# connector_schematic.net
KiCad netlist of a schematic drawn in EAGLE
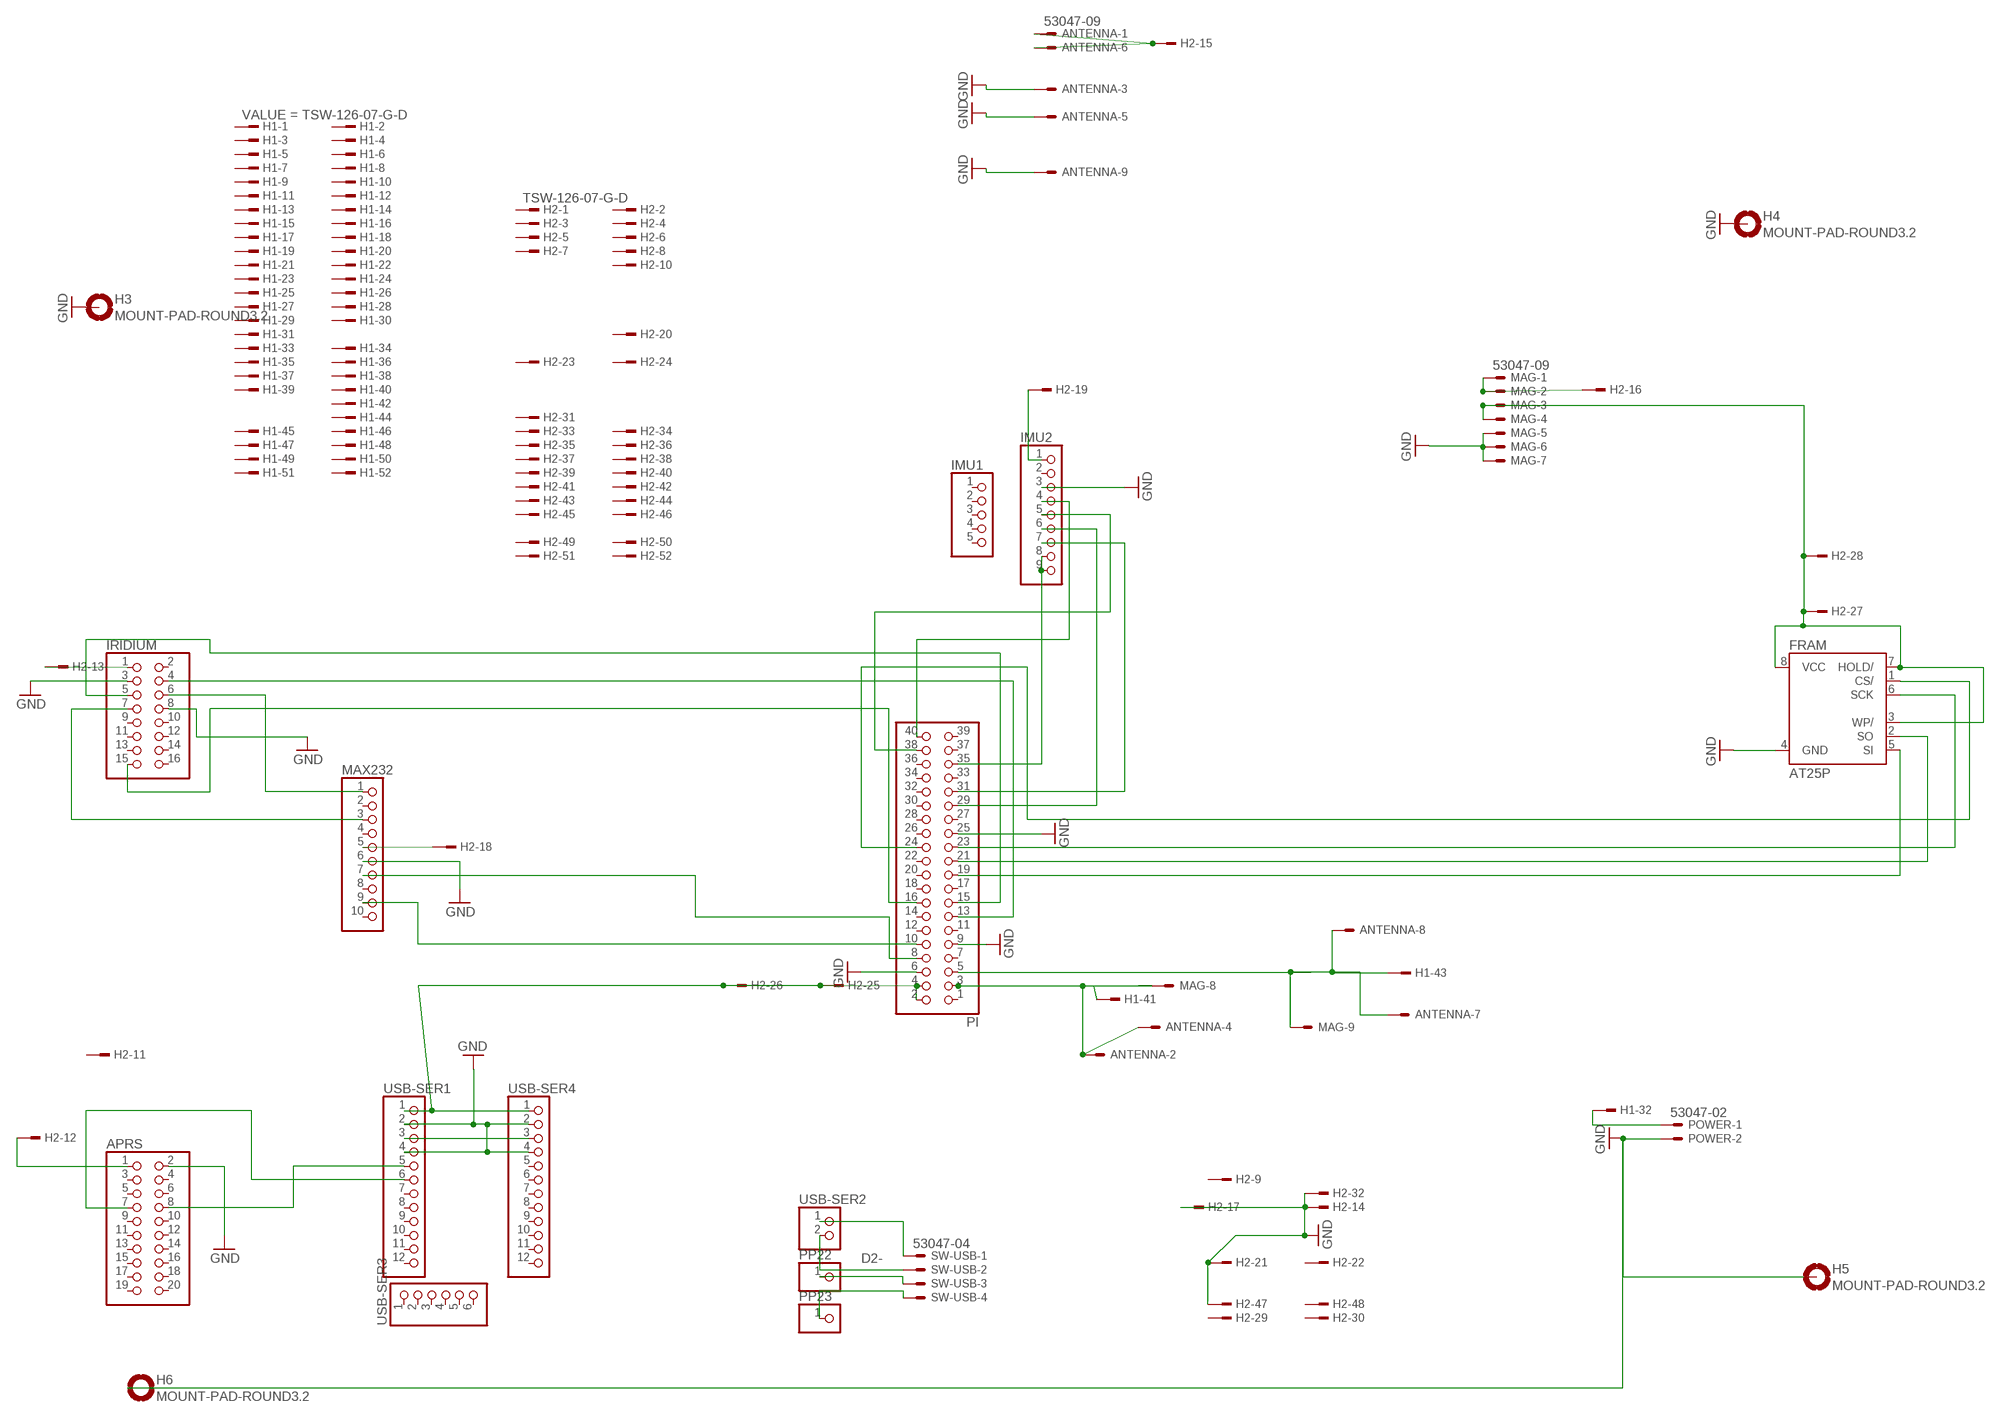
[diagram p0: schematic, sheet 1]

(export (version "E")
  (design (tool "Eeschema 10.0.6"))
  (components
    (comp (ref "ANTENNA")
      (value "53047-09")
      (footprint "eagle-import:53047-09")
      (fields (field (name "MF") "MOLEX") (field (name "MPN") "53047-0910"))
      (libsource (lib "eagle-import") (part "53?-09047"))
    )
    (comp (ref "APRS")
      (value "PINHD-2X10")
      (footprint "eagle-import:2X10")
      (libsource (lib "eagle-import") (part "PINHD-2X10"))
    )
    (comp (ref "FRAM")
      (value "AT25P")
      (footprint "eagle-import:DIL08")
      (fields (field (name "MPN") "CAT25040LI-G"))
      (libsource (lib "eagle-import") (part "AT25P"))
    )
    (comp (ref "H1")
      (value "TSW-126-07-G-D")
      (footprint "eagle-import:TSW-126-XX-G-D")
      (fields (field (name "MF") "Samtec Inc."))
      (libsource (lib "eagle-import") (part "TSW-126--G-D07"))
    )
    (comp (ref "H2")
      (value "TSW-126-07-G-D")
      (footprint "eagle-import:TSW-126-XX-G-D")
      (fields (field (name "MF") "Samtec Inc."))
      (libsource (lib "eagle-import") (part "TSW-126--G-D07"))
    )
    (comp (ref "H3")
      (value "MOUNT-PAD-ROUND3.2")
      (footprint "eagle-import:3,2-PAD")
      (libsource (lib "eagle-import") (part "MOUNT-PAD-ROUND3.2"))
    )
    (comp (ref "H4")
      (value "MOUNT-PAD-ROUND3.2")
      (footprint "eagle-import:3,2-PAD")
      (libsource (lib "eagle-import") (part "MOUNT-PAD-ROUND3.2"))
    )
    (comp (ref "H5")
      (value "MOUNT-PAD-ROUND3.2")
      (footprint "eagle-import:3,2-PAD")
      (libsource (lib "eagle-import") (part "MOUNT-PAD-ROUND3.2"))
    )
    (comp (ref "H6")
      (value "MOUNT-PAD-ROUND3.2")
      (footprint "eagle-import:3,2-PAD")
      (libsource (lib "eagle-import") (part "MOUNT-PAD-ROUND3.2"))
    )
    (comp (ref "IMU1")
      (value "PINHD-1X5")
      (footprint "eagle-import:1X05")
      (libsource (lib "eagle-import") (part "PINHD-1X5"))
    )
    (comp (ref "IMU2")
      (value "PINHD-1X9")
      (footprint "eagle-import:1X09")
      (libsource (lib "eagle-import") (part "PINHD-1X9"))
    )
    (comp (ref "IRIDIUM")
      (value "PINHD-2X8")
      (footprint "eagle-import:2X08")
      (libsource (lib "eagle-import") (part "PINHD-2X8"))
    )
    (comp (ref "MAG")
      (value "53047-09")
      (footprint "eagle-import:53047-09")
      (fields (field (name "MF") "MOLEX") (field (name "MPN") "53047-0910"))
      (libsource (lib "eagle-import") (part "53?-09047"))
    )
    (comp (ref "MAX232")
      (value "PINHD-1X10")
      (footprint "eagle-import:1X10")
      (libsource (lib "eagle-import") (part "PINHD-1X10"))
    )
    (comp (ref "PI")
      (value "PINHD-2X20")
      (footprint "eagle-import:2X20")
      (libsource (lib "eagle-import") (part "PINHD-2X20"))
    )
    (comp (ref "POWER")
      (value "53047-02")
      (footprint "eagle-import:53047-02")
      (fields (field (name "MF") "MOLEX") (field (name "MPN") "53047-0210"))
      (libsource (lib "eagle-import") (part "53?-02047"))
    )
    (comp (ref "PP22")
      (value "PINHD-1X1")
      (footprint "eagle-import:1X01")
      (libsource (lib "eagle-import") (part "PINHD-1X1"))
    )
    (comp (ref "PP23")
      (value "PINHD-1X1")
      (footprint "eagle-import:1X01")
      (libsource (lib "eagle-import") (part "PINHD-1X1"))
    )
    (comp (ref "SW-USB")
      (value "53047-04")
      (footprint "eagle-import:53047-04")
      (fields (field (name "MF") "WALDOM/MOLEX") (field (name "MPN") "53047-0410"))
      (libsource (lib "eagle-import") (part "53?-04047"))
    )
    (comp (ref "USB-SER1")
      (value "PINHD-1X12")
      (footprint "eagle-import:1X12")
      (libsource (lib "eagle-import") (part "PINHD-1X12"))
    )
    (comp (ref "USB-SER2")
      (value "PINHD-1X2")
      (footprint "eagle-import:1X02")
      (libsource (lib "eagle-import") (part "PINHD-1X2"))
    )
    (comp (ref "USB-SER3")
      (value "PINHD-1X6")
      (footprint "eagle-import:1X06")
      (libsource (lib "eagle-import") (part "PINHD-1X6"))
    )
    (comp (ref "USB-SER4")
      (value "PINHD-1X12")
      (footprint "eagle-import:1X12")
      (libsource (lib "eagle-import") (part "PINHD-1X12"))
    )
  )
  (nets
    (net (code "1") (name "/D2-") (class "Default")
      (node (ref "SW-USB") (pin "2") (pinfunction "S_2") (pintype "passive"))
      (node (ref "USB-SER2") (pin "2") (pinfunction "2_2") (pintype "passive"))
    )
    (net (code "2") (name "GND") (class "Default")
      (node (ref "ANTENNA") (pin "3") (pinfunction "S_3") (pintype "passive"))
      (node (ref "ANTENNA") (pin "5") (pinfunction "S_5") (pintype "passive"))
      (node (ref "ANTENNA") (pin "9") (pinfunction "S_9") (pintype "passive"))
      (node (ref "APRS") (pin "2") (pinfunction "2_2") (pintype "passive"))
      (node (ref "FRAM") (pin "4") (pinfunction "GND_4") (pintype "power_in"))
      (node (ref "H2") (pin "14") (pinfunction "1_14") (pintype "passive"))
      (node (ref "H2") (pin "17") (pinfunction "1_17") (pintype "passive"))
      (node (ref "H2") (pin "21") (pinfunction "1_21") (pintype "passive"))
      (node (ref "H2") (pin "32") (pinfunction "1_32") (pintype "passive"))
      (node (ref "H2") (pin "47") (pinfunction "1_47") (pintype "passive"))
      (node (ref "H3") (pin "B3,2") (pinfunction "MOUNT_B3,2") (pintype "passive"))
      (node (ref "H4") (pin "B3,2") (pinfunction "MOUNT_B3,2") (pintype "passive"))
      (node (ref "H5") (pin "B3,2") (pinfunction "MOUNT_B3,2") (pintype "passive"))
      (node (ref "H6") (pin "B3,2") (pinfunction "MOUNT_B3,2") (pintype "passive"))
      (node (ref "IMU2") (pin "3") (pinfunction "3_3") (pintype "passive"))
      (node (ref "IRIDIUM") (pin "3") (pinfunction "3_3") (pintype "passive"))
      (node (ref "IRIDIUM") (pin "8") (pinfunction "8_8") (pintype "passive"))
      (node (ref "MAG") (pin "5") (pinfunction "S_5") (pintype "passive"))
      (node (ref "MAG") (pin "6") (pinfunction "S_6") (pintype "passive"))
      (node (ref "MAG") (pin "7") (pinfunction "S_7") (pintype "passive"))
      (node (ref "MAX232") (pin "6") (pinfunction "6_6") (pintype "passive"))
      (node (ref "PI") (pin "25") (pinfunction "25_25") (pintype "passive"))
      (node (ref "PI") (pin "6") (pinfunction "6_6") (pintype "passive"))
      (node (ref "PI") (pin "9") (pinfunction "9_9") (pintype "passive"))
      (node (ref "POWER") (pin "2") (pinfunction "S_2") (pintype "passive"))
      (node (ref "USB-SER1") (pin "2") (pinfunction "2_2") (pintype "passive"))
      (node (ref "USB-SER1") (pin "4") (pinfunction "4_4") (pintype "passive"))
      (node (ref "USB-SER4") (pin "2") (pinfunction "2_2") (pintype "passive"))
      (node (ref "USB-SER4") (pin "4") (pinfunction "4_4") (pintype "passive"))
    )
    (net (code "3") (name "Net-(ANTENNAA-S)") (class "Default")
      (node (ref "ANTENNA") (pin "1") (pinfunction "S_1") (pintype "passive"))
      (node (ref "ANTENNA") (pin "6") (pinfunction "S_6") (pintype "passive"))
      (node (ref "H2") (pin "15") (pinfunction "1_15") (pintype "passive"))
    )
    (net (code "4") (name "Net-(ANTENNAB-S)") (class "Default")
      (node (ref "ANTENNA") (pin "2") (pinfunction "S_2") (pintype "passive"))
      (node (ref "ANTENNA") (pin "4") (pinfunction "S_4") (pintype "passive"))
      (node (ref "H1") (pin "41") (pinfunction "1_41") (pintype "passive"))
      (node (ref "MAG") (pin "8") (pinfunction "S_8") (pintype "passive"))
      (node (ref "PI") (pin "3") (pinfunction "3_3") (pintype "passive"))
    )
    (net (code "5") (name "Net-(ANTENNAG-S)") (class "Default")
      (node (ref "ANTENNA") (pin "7") (pinfunction "S_7") (pintype "passive"))
      (node (ref "ANTENNA") (pin "8") (pinfunction "S_8") (pintype "passive"))
      (node (ref "H1") (pin "43") (pinfunction "1_43") (pintype "passive"))
      (node (ref "MAG") (pin "9") (pinfunction "S_9") (pintype "passive"))
      (node (ref "PI") (pin "5") (pinfunction "5_5") (pintype "passive"))
    )
    (net (code "6") (name "Net-(APRS-Pad7)") (class "Default")
      (node (ref "APRS") (pin "7") (pinfunction "7_7") (pintype "passive"))
      (node (ref "USB-SER1") (pin "6") (pinfunction "6_6") (pintype "passive"))
    )
    (net (code "7") (name "Net-(APRS-Pad8)") (class "Default")
      (node (ref "APRS") (pin "8") (pinfunction "8_8") (pintype "passive"))
      (node (ref "USB-SER1") (pin "5") (pinfunction "5_5") (pintype "passive"))
    )
    (net (code "8") (name "Net-(FRAM-CS{slash})") (class "Default")
      (node (ref "FRAM") (pin "1") (pinfunction "CS/_1") (pintype "input"))
      (node (ref "PI") (pin "24") (pinfunction "24_24") (pintype "passive"))
    )
    (net (code "9") (name "Net-(FRAM-HOLD{slash})") (class "Default")
      (node (ref "FRAM") (pin "3") (pinfunction "WP/_3") (pintype "input"))
      (node (ref "FRAM") (pin "7") (pinfunction "HOLD/_7") (pintype "input"))
      (node (ref "FRAM") (pin "8") (pinfunction "VCC_8") (pintype "power_in"))
      (node (ref "H2") (pin "27") (pinfunction "1_27") (pintype "passive"))
      (node (ref "H2") (pin "28") (pinfunction "1_28") (pintype "passive"))
      (node (ref "MAG") (pin "3") (pinfunction "S_3") (pintype "passive"))
      (node (ref "MAG") (pin "4") (pinfunction "S_4") (pintype "passive"))
    )
    (net (code "10") (name "Net-(FRAM-SCK)") (class "Default")
      (node (ref "FRAM") (pin "6") (pinfunction "SCK_6") (pintype "bidirectional"))
      (node (ref "PI") (pin "23") (pinfunction "23_23") (pintype "passive"))
    )
    (net (code "11") (name "Net-(FRAM-SI)") (class "Default")
      (node (ref "FRAM") (pin "5") (pinfunction "SI_5") (pintype "bidirectional"))
      (node (ref "PI") (pin "19") (pinfunction "19_19") (pintype "passive"))
    )
    (net (code "12") (name "Net-(FRAM-SO)") (class "Default")
      (node (ref "FRAM") (pin "2") (pinfunction "SO_2") (pintype "input"))
      (node (ref "PI") (pin "21") (pinfunction "21_21") (pintype "passive"))
    )
    (net (code "13") (name "Net-(H1Z-1)") (class "Default")
      (node (ref "H1") (pin "32") (pinfunction "1_32") (pintype "passive"))
      (node (ref "POWER") (pin "1") (pinfunction "S_1") (pintype "passive"))
    )
    (net (code "14") (name "Net-(H2D-1)") (class "Default")
      (node (ref "APRS") (pin "1") (pinfunction "1_1") (pintype "passive"))
      (node (ref "H2") (pin "12") (pinfunction "1_12") (pintype "passive"))
    )
    (net (code "15") (name "Net-(H2E-1)") (class "Default")
      (node (ref "H2") (pin "13") (pinfunction "1_13") (pintype "passive"))
      (node (ref "IRIDIUM") (pin "1") (pinfunction "1_1") (pintype "passive"))
    )
    (net (code "16") (name "Net-(H2H-1)") (class "Default")
      (node (ref "H2") (pin "16") (pinfunction "1_16") (pintype "passive"))
      (node (ref "MAG") (pin "1") (pinfunction "S_1") (pintype "passive"))
      (node (ref "MAG") (pin "2") (pinfunction "S_2") (pintype "passive"))
    )
    (net (code "17") (name "Net-(H2J-1)") (class "Default")
      (node (ref "H2") (pin "18") (pinfunction "1_18") (pintype "passive"))
      (node (ref "MAX232") (pin "5") (pinfunction "5_5") (pintype "passive"))
    )
    (net (code "18") (name "Net-(H2K-1)") (class "Default")
      (node (ref "H2") (pin "19") (pinfunction "1_19") (pintype "passive"))
      (node (ref "IMU2") (pin "1") (pinfunction "1_1") (pintype "passive"))
    )
    (net (code "19") (name "Net-(H2R-1)") (class "Default")
      (node (ref "H2") (pin "25") (pinfunction "1_25") (pintype "passive"))
      (node (ref "H2") (pin "26") (pinfunction "1_26") (pintype "passive"))
      (node (ref "PI") (pin "2") (pinfunction "2_2") (pintype "passive"))
      (node (ref "PI") (pin "4") (pinfunction "4_4") (pintype "passive"))
      (node (ref "USB-SER1") (pin "1") (pinfunction "1_1") (pintype "passive"))
      (node (ref "USB-SER4") (pin "1") (pinfunction "1_1") (pintype "passive"))
    )
    (net (code "20") (name "Net-(IMU2-Pad4)") (class "Default")
      (node (ref "IMU2") (pin "4") (pinfunction "4_4") (pintype "passive"))
      (node (ref "PI") (pin "40") (pinfunction "40_40") (pintype "passive"))
    )
    (net (code "21") (name "Net-(IMU2-Pad5)") (class "Default")
      (node (ref "IMU2") (pin "5") (pinfunction "5_5") (pintype "passive"))
      (node (ref "PI") (pin "38") (pinfunction "38_38") (pintype "passive"))
    )
    (net (code "22") (name "Net-(IMU2-Pad6)") (class "Default")
      (node (ref "IMU2") (pin "6") (pinfunction "6_6") (pintype "passive"))
      (node (ref "PI") (pin "29") (pinfunction "29_29") (pintype "passive"))
    )
    (net (code "23") (name "Net-(IMU2-Pad7)") (class "Default")
      (node (ref "IMU2") (pin "7") (pinfunction "7_7") (pintype "passive"))
      (node (ref "PI") (pin "31") (pinfunction "31_31") (pintype "passive"))
    )
    (net (code "24") (name "Net-(IMU2-Pad8)") (class "Default")
      (node (ref "IMU2") (pin "8") (pinfunction "8_8") (pintype "passive"))
      (node (ref "IMU2") (pin "9") (pinfunction "9_9") (pintype "passive"))
      (node (ref "PI") (pin "35") (pinfunction "35_35") (pintype "passive"))
    )
    (net (code "25") (name "Net-(IRIDIUM-Pad4)") (class "Default")
      (node (ref "IRIDIUM") (pin "4") (pinfunction "4_4") (pintype "passive"))
      (node (ref "PI") (pin "13") (pinfunction "13_13") (pintype "passive"))
    )
    (net (code "26") (name "Net-(IRIDIUM-Pad5)") (class "Default")
      (node (ref "IRIDIUM") (pin "5") (pinfunction "5_5") (pintype "passive"))
      (node (ref "PI") (pin "15") (pinfunction "15_15") (pintype "passive"))
    )
    (net (code "27") (name "Net-(IRIDIUM-Pad6)") (class "Default")
      (node (ref "IRIDIUM") (pin "6") (pinfunction "6_6") (pintype "passive"))
      (node (ref "MAX232") (pin "1") (pinfunction "1_1") (pintype "passive"))
    )
    (net (code "28") (name "Net-(IRIDIUM-Pad7)") (class "Default")
      (node (ref "IRIDIUM") (pin "7") (pinfunction "7_7") (pintype "passive"))
      (node (ref "MAX232") (pin "3") (pinfunction "3_3") (pintype "passive"))
    )
    (net (code "29") (name "Net-(IRIDIUM-Pad15)") (class "Default")
      (node (ref "IRIDIUM") (pin "15") (pinfunction "15_15") (pintype "passive"))
      (node (ref "PI") (pin "16") (pinfunction "16_16") (pintype "passive"))
    )
    (net (code "30") (name "Net-(MAX232-Pad7)") (class "Default")
      (node (ref "MAX232") (pin "7") (pinfunction "7_7") (pintype "passive"))
      (node (ref "PI") (pin "8") (pinfunction "8_8") (pintype "passive"))
    )
    (net (code "31") (name "Net-(MAX232-Pad9)") (class "Default")
      (node (ref "MAX232") (pin "9") (pinfunction "9_9") (pintype "passive"))
      (node (ref "PI") (pin "10") (pinfunction "10_10") (pintype "passive"))
    )
    (net (code "32") (name "Net-(SW-USBA-S)") (class "Default")
      (node (ref "SW-USB") (pin "1") (pinfunction "S_1") (pintype "passive"))
      (node (ref "USB-SER2") (pin "1") (pinfunction "1_1") (pintype "passive"))
    )
    (net (code "33") (name "Net-(SW-USBC-S)") (class "Default")
      (node (ref "PP22") (pin "1") (pinfunction "1_1") (pintype "passive"))
      (node (ref "SW-USB") (pin "3") (pinfunction "S_3") (pintype "passive"))
    )
    (net (code "34") (name "Net-(SW-USBD-S)") (class "Default")
      (node (ref "PP23") (pin "1") (pinfunction "1_1") (pintype "passive"))
      (node (ref "SW-USB") (pin "4") (pinfunction "S_4") (pintype "passive"))
    )
    (net (code "35") (name "Net-(USB-SER1-Pad3)") (class "Default")
      (node (ref "USB-SER1") (pin "3") (pinfunction "3_3") (pintype "passive"))
      (node (ref "USB-SER4") (pin "3") (pinfunction "3_3") (pintype "passive"))
    )
    (net (code "36") (name "unconnected-(APRS-Pad3)") (class "Default")
      (node (ref "APRS") (pin "3") (pinfunction "3_3") (pintype "passive"))
    )
    (net (code "37") (name "unconnected-(APRS-Pad4)") (class "Default")
      (node (ref "APRS") (pin "4") (pinfunction "4_4") (pintype "passive"))
    )
    (net (code "38") (name "unconnected-(APRS-Pad5)") (class "Default")
      (node (ref "APRS") (pin "5") (pinfunction "5_5") (pintype "passive"))
    )
    (net (code "39") (name "unconnected-(APRS-Pad6)") (class "Default")
      (node (ref "APRS") (pin "6") (pinfunction "6_6") (pintype "passive"))
    )
    (net (code "40") (name "unconnected-(APRS-Pad9)") (class "Default")
      (node (ref "APRS") (pin "9") (pinfunction "9_9") (pintype "passive"))
    )
    (net (code "41") (name "unconnected-(APRS-Pad10)") (class "Default")
      (node (ref "APRS") (pin "10") (pinfunction "10_10") (pintype "passive"))
    )
    (net (code "42") (name "unconnected-(APRS-Pad11)") (class "Default")
      (node (ref "APRS") (pin "11") (pinfunction "11_11") (pintype "passive"))
    )
    (net (code "43") (name "unconnected-(APRS-Pad12)") (class "Default")
      (node (ref "APRS") (pin "12") (pinfunction "12_12") (pintype "passive"))
    )
    (net (code "44") (name "unconnected-(APRS-Pad13)") (class "Default")
      (node (ref "APRS") (pin "13") (pinfunction "13_13") (pintype "passive"))
    )
    (net (code "45") (name "unconnected-(APRS-Pad14)") (class "Default")
      (node (ref "APRS") (pin "14") (pinfunction "14_14") (pintype "passive"))
    )
    (net (code "46") (name "unconnected-(APRS-Pad15)") (class "Default")
      (node (ref "APRS") (pin "15") (pinfunction "15_15") (pintype "passive"))
    )
    (net (code "47") (name "unconnected-(APRS-Pad16)") (class "Default")
      (node (ref "APRS") (pin "16") (pinfunction "16_16") (pintype "passive"))
    )
    (net (code "48") (name "unconnected-(APRS-Pad17)") (class "Default")
      (node (ref "APRS") (pin "17") (pinfunction "17_17") (pintype "passive"))
    )
    (net (code "49") (name "unconnected-(APRS-Pad18)") (class "Default")
      (node (ref "APRS") (pin "18") (pinfunction "18_18") (pintype "passive"))
    )
    (net (code "50") (name "unconnected-(APRS-Pad19)") (class "Default")
      (node (ref "APRS") (pin "19") (pinfunction "19_19") (pintype "passive"))
    )
    (net (code "51") (name "unconnected-(APRS-Pad20)") (class "Default")
      (node (ref "APRS") (pin "20") (pinfunction "20_20") (pintype "passive"))
    )
    (net (code "52") (name "unconnected-(H1-Pad1)") (class "Default")
      (node (ref "H1") (pin "1") (pinfunction "1_1") (pintype "passive"))
    )
    (net (code "53") (name "unconnected-(H1AA-1-Pad33)") (class "Default")
      (node (ref "H1") (pin "33") (pinfunction "1_33") (pintype "passive"))
    )
    (net (code "54") (name "unconnected-(H1AB-1-Pad34)") (class "Default")
      (node (ref "H1") (pin "34") (pinfunction "1_34") (pintype "passive"))
    )
    (net (code "55") (name "unconnected-(H1AC-1-Pad35)") (class "Default")
      (node (ref "H1") (pin "35") (pinfunction "1_35") (pintype "passive"))
    )
    (net (code "56") (name "unconnected-(H1AD-1-Pad36)") (class "Default")
      (node (ref "H1") (pin "36") (pinfunction "1_36") (pintype "passive"))
    )
    (net (code "57") (name "unconnected-(H1AE-1-Pad37)") (class "Default")
      (node (ref "H1") (pin "37") (pinfunction "1_37") (pintype "passive"))
    )
    (net (code "58") (name "unconnected-(H1AF-1-Pad38)") (class "Default")
      (node (ref "H1") (pin "38") (pinfunction "1_38") (pintype "passive"))
    )
    (net (code "59") (name "unconnected-(H1AG-1-Pad39)") (class "Default")
      (node (ref "H1") (pin "39") (pinfunction "1_39") (pintype "passive"))
    )
    (net (code "60") (name "unconnected-(H1AH-1-Pad4)") (class "Default")
      (node (ref "H1") (pin "4") (pinfunction "1_4") (pintype "passive"))
    )
    (net (code "61") (name "unconnected-(H1AI-1-Pad40)") (class "Default")
      (node (ref "H1") (pin "40") (pinfunction "1_40") (pintype "passive"))
    )
    (net (code "62") (name "unconnected-(H1AK-1-Pad42)") (class "Default")
      (node (ref "H1") (pin "42") (pinfunction "1_42") (pintype "passive"))
    )
    (net (code "63") (name "unconnected-(H1AM-1-Pad44)") (class "Default")
      (node (ref "H1") (pin "44") (pinfunction "1_44") (pintype "passive"))
    )
    (net (code "64") (name "unconnected-(H1AN-1-Pad45)") (class "Default")
      (node (ref "H1") (pin "45") (pinfunction "1_45") (pintype "passive"))
    )
    (net (code "65") (name "unconnected-(H1AO-1-Pad46)") (class "Default")
      (node (ref "H1") (pin "46") (pinfunction "1_46") (pintype "passive"))
    )
    (net (code "66") (name "unconnected-(H1AP-1-Pad47)") (class "Default")
      (node (ref "H1") (pin "47") (pinfunction "1_47") (pintype "passive"))
    )
    (net (code "67") (name "unconnected-(H1AQ-1-Pad48)") (class "Default")
      (node (ref "H1") (pin "48") (pinfunction "1_48") (pintype "passive"))
    )
    (net (code "68") (name "unconnected-(H1AR-1-Pad49)") (class "Default")
      (node (ref "H1") (pin "49") (pinfunction "1_49") (pintype "passive"))
    )
    (net (code "69") (name "unconnected-(H1AS-1-Pad5)") (class "Default")
      (node (ref "H1") (pin "5") (pinfunction "1_5") (pintype "passive"))
    )
    (net (code "70") (name "unconnected-(H1AT-1-Pad50)") (class "Default")
      (node (ref "H1") (pin "50") (pinfunction "1_50") (pintype "passive"))
    )
    (net (code "71") (name "unconnected-(H1AU-1-Pad51)") (class "Default")
      (node (ref "H1") (pin "51") (pinfunction "1_51") (pintype "passive"))
    )
    (net (code "72") (name "unconnected-(H1AV-1-Pad52)") (class "Default")
      (node (ref "H1") (pin "52") (pinfunction "1_52") (pintype "passive"))
    )
    (net (code "73") (name "unconnected-(H1AW-1-Pad6)") (class "Default")
      (node (ref "H1") (pin "6") (pinfunction "1_6") (pintype "passive"))
    )
    (net (code "74") (name "unconnected-(H1AX-1-Pad7)") (class "Default")
      (node (ref "H1") (pin "7") (pinfunction "1_7") (pintype "passive"))
    )
    (net (code "75") (name "unconnected-(H1AY-1-Pad8)") (class "Default")
      (node (ref "H1") (pin "8") (pinfunction "1_8") (pintype "passive"))
    )
    (net (code "76") (name "unconnected-(H1AZ-1-Pad9)") (class "Default")
      (node (ref "H1") (pin "9") (pinfunction "1_9") (pintype "passive"))
    )
    (net (code "77") (name "unconnected-(H1B-1-Pad10)") (class "Default")
      (node (ref "H1") (pin "10") (pinfunction "1_10") (pintype "passive"))
    )
    (net (code "78") (name "unconnected-(H1C-1-Pad11)") (class "Default")
      (node (ref "H1") (pin "11") (pinfunction "1_11") (pintype "passive"))
    )
    (net (code "79") (name "unconnected-(H1D-1-Pad12)") (class "Default")
      (node (ref "H1") (pin "12") (pinfunction "1_12") (pintype "passive"))
    )
    (net (code "80") (name "unconnected-(H1E-1-Pad13)") (class "Default")
      (node (ref "H1") (pin "13") (pinfunction "1_13") (pintype "passive"))
    )
    (net (code "81") (name "unconnected-(H1F-1-Pad14)") (class "Default")
      (node (ref "H1") (pin "14") (pinfunction "1_14") (pintype "passive"))
    )
    (net (code "82") (name "unconnected-(H1G-1-Pad15)") (class "Default")
      (node (ref "H1") (pin "15") (pinfunction "1_15") (pintype "passive"))
    )
    (net (code "83") (name "unconnected-(H1H-1-Pad16)") (class "Default")
      (node (ref "H1") (pin "16") (pinfunction "1_16") (pintype "passive"))
    )
    (net (code "84") (name "unconnected-(H1I-1-Pad17)") (class "Default")
      (node (ref "H1") (pin "17") (pinfunction "1_17") (pintype "passive"))
    )
    (net (code "85") (name "unconnected-(H1J-1-Pad18)") (class "Default")
      (node (ref "H1") (pin "18") (pinfunction "1_18") (pintype "passive"))
    )
    (net (code "86") (name "unconnected-(H1K-1-Pad19)") (class "Default")
      (node (ref "H1") (pin "19") (pinfunction "1_19") (pintype "passive"))
    )
    (net (code "87") (name "unconnected-(H1L-1-Pad2)") (class "Default")
      (node (ref "H1") (pin "2") (pinfunction "1_2") (pintype "passive"))
    )
    (net (code "88") (name "unconnected-(H1M-1-Pad20)") (class "Default")
      (node (ref "H1") (pin "20") (pinfunction "1_20") (pintype "passive"))
    )
    (net (code "89") (name "unconnected-(H1N-1-Pad21)") (class "Default")
      (node (ref "H1") (pin "21") (pinfunction "1_21") (pintype "passive"))
    )
    (net (code "90") (name "unconnected-(H1O-1-Pad22)") (class "Default")
      (node (ref "H1") (pin "22") (pinfunction "1_22") (pintype "passive"))
    )
    (net (code "91") (name "unconnected-(H1P-1-Pad23)") (class "Default")
      (node (ref "H1") (pin "23") (pinfunction "1_23") (pintype "passive"))
    )
    (net (code "92") (name "unconnected-(H1Q-1-Pad24)") (class "Default")
      (node (ref "H1") (pin "24") (pinfunction "1_24") (pintype "passive"))
    )
    (net (code "93") (name "unconnected-(H1R-1-Pad25)") (class "Default")
      (node (ref "H1") (pin "25") (pinfunction "1_25") (pintype "passive"))
    )
    (net (code "94") (name "unconnected-(H1S-1-Pad26)") (class "Default")
      (node (ref "H1") (pin "26") (pinfunction "1_26") (pintype "passive"))
    )
    (net (code "95") (name "unconnected-(H1T-1-Pad27)") (class "Default")
      (node (ref "H1") (pin "27") (pinfunction "1_27") (pintype "passive"))
    )
    (net (code "96") (name "unconnected-(H1U-1-Pad28)") (class "Default")
      (node (ref "H1") (pin "28") (pinfunction "1_28") (pintype "passive"))
    )
    (net (code "97") (name "unconnected-(H1V-1-Pad29)") (class "Default")
      (node (ref "H1") (pin "29") (pinfunction "1_29") (pintype "passive"))
    )
    (net (code "98") (name "unconnected-(H1W-1-Pad3)") (class "Default")
      (node (ref "H1") (pin "3") (pinfunction "1_3") (pintype "passive"))
    )
    (net (code "99") (name "unconnected-(H1X-1-Pad30)") (class "Default")
      (node (ref "H1") (pin "30") (pinfunction "1_30") (pintype "passive"))
    )
    (net (code "100") (name "unconnected-(H1Y-1-Pad31)") (class "Default")
      (node (ref "H1") (pin "31") (pinfunction "1_31") (pintype "passive"))
    )
    (net (code "101") (name "unconnected-(H2-Pad1)") (class "Default")
      (node (ref "H2") (pin "1") (pinfunction "1_1") (pintype "passive"))
    )
    (net (code "102") (name "unconnected-(H2AA-1-Pad33)") (class "Default")
      (node (ref "H2") (pin "33") (pinfunction "1_33") (pintype "passive"))
    )
    (net (code "103") (name "unconnected-(H2AB-1-Pad34)") (class "Default")
      (node (ref "H2") (pin "34") (pinfunction "1_34") (pintype "passive"))
    )
    (net (code "104") (name "unconnected-(H2AC-1-Pad35)") (class "Default")
      (node (ref "H2") (pin "35") (pinfunction "1_35") (pintype "passive"))
    )
    (net (code "105") (name "unconnected-(H2AD-1-Pad36)") (class "Default")
      (node (ref "H2") (pin "36") (pinfunction "1_36") (pintype "passive"))
    )
    (net (code "106") (name "unconnected-(H2AE-1-Pad37)") (class "Default")
      (node (ref "H2") (pin "37") (pinfunction "1_37") (pintype "passive"))
    )
    (net (code "107") (name "unconnected-(H2AF-1-Pad38)") (class "Default")
      (node (ref "H2") (pin "38") (pinfunction "1_38") (pintype "passive"))
    )
    (net (code "108") (name "unconnected-(H2AG-1-Pad39)") (class "Default")
      (node (ref "H2") (pin "39") (pinfunction "1_39") (pintype "passive"))
    )
    (net (code "109") (name "unconnected-(H2AH-1-Pad4)") (class "Default")
      (node (ref "H2") (pin "4") (pinfunction "1_4") (pintype "passive"))
    )
    (net (code "110") (name "unconnected-(H2AI-1-Pad40)") (class "Default")
      (node (ref "H2") (pin "40") (pinfunction "1_40") (pintype "passive"))
    )
    (net (code "111") (name "unconnected-(H2AJ-1-Pad41)") (class "Default")
      (node (ref "H2") (pin "41") (pinfunction "1_41") (pintype "passive"))
    )
    (net (code "112") (name "unconnected-(H2AK-1-Pad42)") (class "Default")
      (node (ref "H2") (pin "42") (pinfunction "1_42") (pintype "passive"))
    )
    (net (code "113") (name "unconnected-(H2AL-1-Pad43)") (class "Default")
      (node (ref "H2") (pin "43") (pinfunction "1_43") (pintype "passive"))
    )
    (net (code "114") (name "unconnected-(H2AM-1-Pad44)") (class "Default")
      (node (ref "H2") (pin "44") (pinfunction "1_44") (pintype "passive"))
    )
    (net (code "115") (name "unconnected-(H2AN-1-Pad45)") (class "Default")
      (node (ref "H2") (pin "45") (pinfunction "1_45") (pintype "passive"))
    )
    (net (code "116") (name "unconnected-(H2AO-1-Pad46)") (class "Default")
      (node (ref "H2") (pin "46") (pinfunction "1_46") (pintype "passive"))
    )
    (net (code "117") (name "unconnected-(H2AQ-1-Pad48)") (class "Default")
      (node (ref "H2") (pin "48") (pinfunction "1_48") (pintype "passive"))
    )
    (net (code "118") (name "unconnected-(H2AR-1-Pad49)") (class "Default")
      (node (ref "H2") (pin "49") (pinfunction "1_49") (pintype "passive"))
    )
    (net (code "119") (name "unconnected-(H2AS-1-Pad5)") (class "Default")
      (node (ref "H2") (pin "5") (pinfunction "1_5") (pintype "passive"))
    )
    (net (code "120") (name "unconnected-(H2AT-1-Pad50)") (class "Default")
      (node (ref "H2") (pin "50") (pinfunction "1_50") (pintype "passive"))
    )
    (net (code "121") (name "unconnected-(H2AU-1-Pad51)") (class "Default")
      (node (ref "H2") (pin "51") (pinfunction "1_51") (pintype "passive"))
    )
    (net (code "122") (name "unconnected-(H2AV-1-Pad52)") (class "Default")
      (node (ref "H2") (pin "52") (pinfunction "1_52") (pintype "passive"))
    )
    (net (code "123") (name "unconnected-(H2AW-1-Pad6)") (class "Default")
      (node (ref "H2") (pin "6") (pinfunction "1_6") (pintype "passive"))
    )
    (net (code "124") (name "unconnected-(H2AX-1-Pad7)") (class "Default")
      (node (ref "H2") (pin "7") (pinfunction "1_7") (pintype "passive"))
    )
    (net (code "125") (name "unconnected-(H2AY-1-Pad8)") (class "Default")
      (node (ref "H2") (pin "8") (pinfunction "1_8") (pintype "passive"))
    )
    (net (code "126") (name "unconnected-(H2AZ-1-Pad9)") (class "Default")
      (node (ref "H2") (pin "9") (pinfunction "1_9") (pintype "passive"))
    )
    (net (code "127") (name "unconnected-(H2B-1-Pad10)") (class "Default")
      (node (ref "H2") (pin "10") (pinfunction "1_10") (pintype "passive"))
    )
    (net (code "128") (name "unconnected-(H2C-1-Pad11)") (class "Default")
      (node (ref "H2") (pin "11") (pinfunction "1_11") (pintype "passive"))
    )
    (net (code "129") (name "unconnected-(H2L-1-Pad2)") (class "Default")
      (node (ref "H2") (pin "2") (pinfunction "1_2") (pintype "passive"))
    )
    (net (code "130") (name "unconnected-(H2M-1-Pad20)") (class "Default")
      (node (ref "H2") (pin "20") (pinfunction "1_20") (pintype "passive"))
    )
    (net (code "131") (name "unconnected-(H2O-1-Pad22)") (class "Default")
      (node (ref "H2") (pin "22") (pinfunction "1_22") (pintype "passive"))
    )
    (net (code "132") (name "unconnected-(H2P-1-Pad23)") (class "Default")
      (node (ref "H2") (pin "23") (pinfunction "1_23") (pintype "passive"))
    )
    (net (code "133") (name "unconnected-(H2Q-1-Pad24)") (class "Default")
      (node (ref "H2") (pin "24") (pinfunction "1_24") (pintype "passive"))
    )
    (net (code "134") (name "unconnected-(H2V-1-Pad29)") (class "Default")
      (node (ref "H2") (pin "29") (pinfunction "1_29") (pintype "passive"))
    )
    (net (code "135") (name "unconnected-(H2W-1-Pad3)") (class "Default")
      (node (ref "H2") (pin "3") (pinfunction "1_3") (pintype "passive"))
    )
    (net (code "136") (name "unconnected-(H2X-1-Pad30)") (class "Default")
      (node (ref "H2") (pin "30") (pinfunction "1_30") (pintype "passive"))
    )
    (net (code "137") (name "unconnected-(H2Y-1-Pad31)") (class "Default")
      (node (ref "H2") (pin "31") (pinfunction "1_31") (pintype "passive"))
    )
    (net (code "138") (name "unconnected-(IMU1-Pad1)") (class "Default")
      (node (ref "IMU1") (pin "1") (pinfunction "1_1") (pintype "passive"))
    )
    (net (code "139") (name "unconnected-(IMU1-Pad2)") (class "Default")
      (node (ref "IMU1") (pin "2") (pinfunction "2_2") (pintype "passive"))
    )
    (net (code "140") (name "unconnected-(IMU1-Pad3)") (class "Default")
      (node (ref "IMU1") (pin "3") (pinfunction "3_3") (pintype "passive"))
    )
    (net (code "141") (name "unconnected-(IMU1-Pad4)") (class "Default")
      (node (ref "IMU1") (pin "4") (pinfunction "4_4") (pintype "passive"))
    )
    (net (code "142") (name "unconnected-(IMU1-Pad5)") (class "Default")
      (node (ref "IMU1") (pin "5") (pinfunction "5_5") (pintype "passive"))
    )
    (net (code "143") (name "unconnected-(IMU2-Pad2)") (class "Default")
      (node (ref "IMU2") (pin "2") (pinfunction "2_2") (pintype "passive"))
    )
    (net (code "144") (name "unconnected-(IRIDIUM-Pad2)") (class "Default")
      (node (ref "IRIDIUM") (pin "2") (pinfunction "2_2") (pintype "passive"))
    )
    (net (code "145") (name "unconnected-(IRIDIUM-Pad9)") (class "Default")
      (node (ref "IRIDIUM") (pin "9") (pinfunction "9_9") (pintype "passive"))
    )
    (net (code "146") (name "unconnected-(IRIDIUM-Pad10)") (class "Default")
      (node (ref "IRIDIUM") (pin "10") (pinfunction "10_10") (pintype "passive"))
    )
    (net (code "147") (name "unconnected-(IRIDIUM-Pad11)") (class "Default")
      (node (ref "IRIDIUM") (pin "11") (pinfunction "11_11") (pintype "passive"))
    )
    (net (code "148") (name "unconnected-(IRIDIUM-Pad12)") (class "Default")
      (node (ref "IRIDIUM") (pin "12") (pinfunction "12_12") (pintype "passive"))
    )
    (net (code "149") (name "unconnected-(IRIDIUM-Pad13)") (class "Default")
      (node (ref "IRIDIUM") (pin "13") (pinfunction "13_13") (pintype "passive"))
    )
    (net (code "150") (name "unconnected-(IRIDIUM-Pad14)") (class "Default")
      (node (ref "IRIDIUM") (pin "14") (pinfunction "14_14") (pintype "passive"))
    )
    (net (code "151") (name "unconnected-(IRIDIUM-Pad16)") (class "Default")
      (node (ref "IRIDIUM") (pin "16") (pinfunction "16_16") (pintype "passive"))
    )
    (net (code "152") (name "unconnected-(MAX232-Pad2)") (class "Default")
      (node (ref "MAX232") (pin "2") (pinfunction "2_2") (pintype "passive"))
    )
    (net (code "153") (name "unconnected-(MAX232-Pad4)") (class "Default")
      (node (ref "MAX232") (pin "4") (pinfunction "4_4") (pintype "passive"))
    )
    (net (code "154") (name "unconnected-(MAX232-Pad8)") (class "Default")
      (node (ref "MAX232") (pin "8") (pinfunction "8_8") (pintype "passive"))
    )
    (net (code "155") (name "unconnected-(MAX232-Pad10)") (class "Default")
      (node (ref "MAX232") (pin "10") (pinfunction "10_10") (pintype "passive"))
    )
    (net (code "156") (name "unconnected-(PI-Pad1)") (class "Default")
      (node (ref "PI") (pin "1") (pinfunction "1_1") (pintype "passive"))
    )
    (net (code "157") (name "unconnected-(PI-Pad7)") (class "Default")
      (node (ref "PI") (pin "7") (pinfunction "7_7") (pintype "passive"))
    )
    (net (code "158") (name "unconnected-(PI-Pad11)") (class "Default")
      (node (ref "PI") (pin "11") (pinfunction "11_11") (pintype "passive"))
    )
    (net (code "159") (name "unconnected-(PI-Pad12)") (class "Default")
      (node (ref "PI") (pin "12") (pinfunction "12_12") (pintype "passive"))
    )
    (net (code "160") (name "unconnected-(PI-Pad14)") (class "Default")
      (node (ref "PI") (pin "14") (pinfunction "14_14") (pintype "passive"))
    )
    (net (code "161") (name "unconnected-(PI-Pad17)") (class "Default")
      (node (ref "PI") (pin "17") (pinfunction "17_17") (pintype "passive"))
    )
    (net (code "162") (name "unconnected-(PI-Pad18)") (class "Default")
      (node (ref "PI") (pin "18") (pinfunction "18_18") (pintype "passive"))
    )
    (net (code "163") (name "unconnected-(PI-Pad20)") (class "Default")
      (node (ref "PI") (pin "20") (pinfunction "20_20") (pintype "passive"))
    )
    (net (code "164") (name "unconnected-(PI-Pad22)") (class "Default")
      (node (ref "PI") (pin "22") (pinfunction "22_22") (pintype "passive"))
    )
    (net (code "165") (name "unconnected-(PI-Pad26)") (class "Default")
      (node (ref "PI") (pin "26") (pinfunction "26_26") (pintype "passive"))
    )
    (net (code "166") (name "unconnected-(PI-Pad27)") (class "Default")
      (node (ref "PI") (pin "27") (pinfunction "27_27") (pintype "passive"))
    )
    (net (code "167") (name "unconnected-(PI-Pad28)") (class "Default")
      (node (ref "PI") (pin "28") (pinfunction "28_28") (pintype "passive"))
    )
    (net (code "168") (name "unconnected-(PI-Pad30)") (class "Default")
      (node (ref "PI") (pin "30") (pinfunction "30_30") (pintype "passive"))
    )
    (net (code "169") (name "unconnected-(PI-Pad32)") (class "Default")
      (node (ref "PI") (pin "32") (pinfunction "32_32") (pintype "passive"))
    )
    (net (code "170") (name "unconnected-(PI-Pad33)") (class "Default")
      (node (ref "PI") (pin "33") (pinfunction "33_33") (pintype "passive"))
    )
    (net (code "171") (name "unconnected-(PI-Pad34)") (class "Default")
      (node (ref "PI") (pin "34") (pinfunction "34_34") (pintype "passive"))
    )
    (net (code "172") (name "unconnected-(PI-Pad36)") (class "Default")
      (node (ref "PI") (pin "36") (pinfunction "36_36") (pintype "passive"))
    )
    (net (code "173") (name "unconnected-(PI-Pad37)") (class "Default")
      (node (ref "PI") (pin "37") (pinfunction "37_37") (pintype "passive"))
    )
    (net (code "174") (name "unconnected-(PI-Pad39)") (class "Default")
      (node (ref "PI") (pin "39") (pinfunction "39_39") (pintype "passive"))
    )
    (net (code "175") (name "unconnected-(USB-SER1-Pad7)") (class "Default")
      (node (ref "USB-SER1") (pin "7") (pinfunction "7_7") (pintype "passive"))
    )
    (net (code "176") (name "unconnected-(USB-SER1-Pad8)") (class "Default")
      (node (ref "USB-SER1") (pin "8") (pinfunction "8_8") (pintype "passive"))
    )
    (net (code "177") (name "unconnected-(USB-SER1-Pad9)") (class "Default")
      (node (ref "USB-SER1") (pin "9") (pinfunction "9_9") (pintype "passive"))
    )
    (net (code "178") (name "unconnected-(USB-SER1-Pad10)") (class "Default")
      (node (ref "USB-SER1") (pin "10") (pinfunction "10_10") (pintype "passive"))
    )
    (net (code "179") (name "unconnected-(USB-SER1-Pad11)") (class "Default")
      (node (ref "USB-SER1") (pin "11") (pinfunction "11_11") (pintype "passive"))
    )
    (net (code "180") (name "unconnected-(USB-SER1-Pad12)") (class "Default")
      (node (ref "USB-SER1") (pin "12") (pinfunction "12_12") (pintype "passive"))
    )
    (net (code "181") (name "unconnected-(USB-SER3-Pad1)") (class "Default")
      (node (ref "USB-SER3") (pin "1") (pinfunction "1_1") (pintype "passive"))
    )
    (net (code "182") (name "unconnected-(USB-SER3-Pad2)") (class "Default")
      (node (ref "USB-SER3") (pin "2") (pinfunction "2_2") (pintype "passive"))
    )
    (net (code "183") (name "unconnected-(USB-SER3-Pad3)") (class "Default")
      (node (ref "USB-SER3") (pin "3") (pinfunction "3_3") (pintype "passive"))
    )
    (net (code "184") (name "unconnected-(USB-SER3-Pad4)") (class "Default")
      (node (ref "USB-SER3") (pin "4") (pinfunction "4_4") (pintype "passive"))
    )
    (net (code "185") (name "unconnected-(USB-SER3-Pad5)") (class "Default")
      (node (ref "USB-SER3") (pin "5") (pinfunction "5_5") (pintype "passive"))
    )
    (net (code "186") (name "unconnected-(USB-SER3-Pad6)") (class "Default")
      (node (ref "USB-SER3") (pin "6") (pinfunction "6_6") (pintype "passive"))
    )
    (net (code "187") (name "unconnected-(USB-SER4-Pad5)") (class "Default")
      (node (ref "USB-SER4") (pin "5") (pinfunction "5_5") (pintype "passive"))
    )
    (net (code "188") (name "unconnected-(USB-SER4-Pad6)") (class "Default")
      (node (ref "USB-SER4") (pin "6") (pinfunction "6_6") (pintype "passive"))
    )
    (net (code "189") (name "unconnected-(USB-SER4-Pad7)") (class "Default")
      (node (ref "USB-SER4") (pin "7") (pinfunction "7_7") (pintype "passive"))
    )
    (net (code "190") (name "unconnected-(USB-SER4-Pad8)") (class "Default")
      (node (ref "USB-SER4") (pin "8") (pinfunction "8_8") (pintype "passive"))
    )
    (net (code "191") (name "unconnected-(USB-SER4-Pad9)") (class "Default")
      (node (ref "USB-SER4") (pin "9") (pinfunction "9_9") (pintype "passive"))
    )
    (net (code "192") (name "unconnected-(USB-SER4-Pad10)") (class "Default")
      (node (ref "USB-SER4") (pin "10") (pinfunction "10_10") (pintype "passive"))
    )
    (net (code "193") (name "unconnected-(USB-SER4-Pad11)") (class "Default")
      (node (ref "USB-SER4") (pin "11") (pinfunction "11_11") (pintype "passive"))
    )
    (net (code "194") (name "unconnected-(USB-SER4-Pad12)") (class "Default")
      (node (ref "USB-SER4") (pin "12") (pinfunction "12_12") (pintype "passive"))
    )
  )
)
